# Motor_Controller.net
KiCad netlist of a schematic drawn in EAGLE
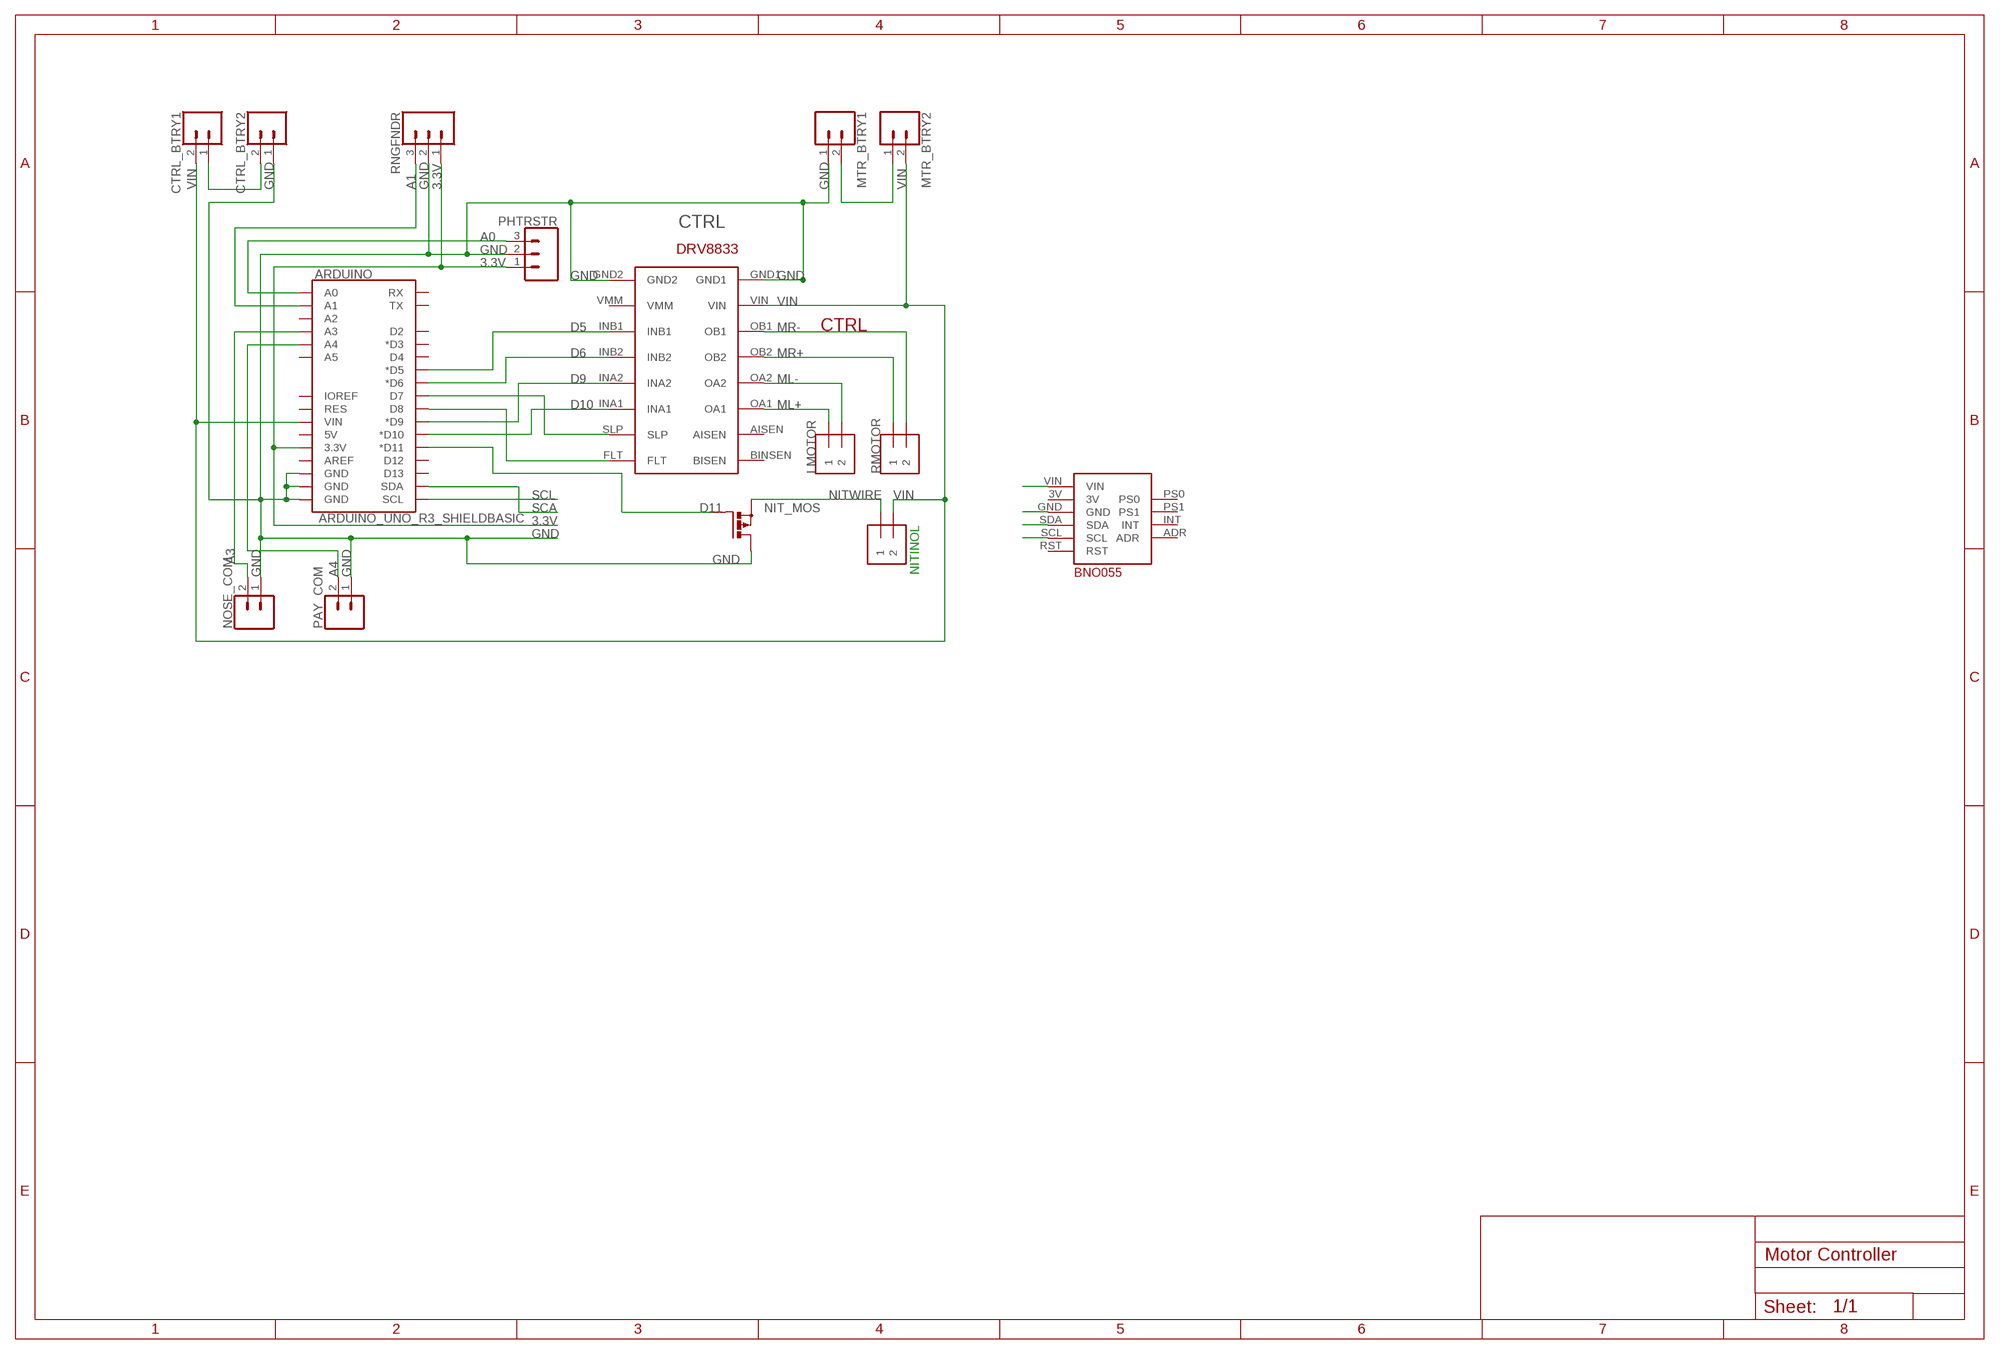
[diagram p0: schematic, sheet 1]

(export (version "E")
  (design (tool "Eeschema 10.0.6"))
  (components
    (comp (ref "ARDUINO")
      (value "ARDUINO_UNO_R3_SHIELDBASIC")
      (footprint "eagle-import:UNO_R3_SHIELD")
      (libsource (lib "eagle-import") (part "ARDUINO_UNO_R3_SHIELDBASIC"))
    )
    (comp (ref "CTRL")
      (value "POLOLU-DRV8833")
      (footprint "eagle-import:POLOLU-DRV8833")
      (libsource (lib "eagle-import") (part "POLOLU-DRV8833"))
    )
    (comp (ref "CTRL_BTRY1")
      (value "CONN_02-JST-2-PTH-NO_SILK")
      (footprint "eagle-import:JST-2-PTH-NS")
      (libsource (lib "eagle-import") (part "CONN_02-JST-2-PTH-NO_SILK"))
    )
    (comp (ref "CTRL_BTRY2")
      (value "CONN_02-JST-2-PTH-NO_SILK")
      (footprint "eagle-import:JST-2-PTH-NS")
      (libsource (lib "eagle-import") (part "CONN_02-JST-2-PTH-NO_SILK"))
    )
    (comp (ref "LMOTOR")
      (value "1X2-3.5MM")
      (footprint "eagle-import:1X2-3.5MM")
      (libsource (lib "eagle-import") (part "1X2-3.5MM"))
    )
    (comp (ref "MTR_BTRY1")
      (value "CONN_02-JST-2-PTH-NO_SILK")
      (footprint "eagle-import:JST-2-PTH-NS")
      (libsource (lib "eagle-import") (part "CONN_02-JST-2-PTH-NO_SILK"))
    )
    (comp (ref "MTR_BTRY2")
      (value "CONN_02-JST-2-PTH-NO_SILK")
      (footprint "eagle-import:JST-2-PTH-NS")
      (libsource (lib "eagle-import") (part "CONN_02-JST-2-PTH-NO_SILK"))
    )
    (comp (ref "NITINOL")
      (value "1X2-3.5MM")
      (footprint "eagle-import:1X2-3.5MM")
      (libsource (lib "eagle-import") (part "1X2-3.5MM"))
    )
    (comp (ref "NIT_MOS")
      (value "PMOSFET_PTO220BH")
      (footprint "eagle-import:TO220BH")
      (libsource (lib "eagle-import") (part "PMOSFET_PTO220BH"))
    )
    (comp (ref "NOSE_COM")
      (value "CONN_02JST-PTH-2")
      (footprint "eagle-import:JST-2-PTH")
      (libsource (lib "eagle-import") (part "CONN_02JST-PTH-2"))
    )
    (comp (ref "PAY_COM")
      (value "CONN_02JST-PTH-2")
      (footprint "eagle-import:JST-2-PTH")
      (libsource (lib "eagle-import") (part "CONN_02JST-PTH-2"))
    )
    (comp (ref "PHTRSTR")
      (value "CONN_03JST-PTH-NS")
      (footprint "eagle-import:JST-3-PTH-NS")
      (libsource (lib "eagle-import") (part "CONN_03JST-PTH-NS"))
    )
    (comp (ref "RMOTOR")
      (value "1X2-3.5MM")
      (footprint "eagle-import:1X2-3.5MM")
      (libsource (lib "eagle-import") (part "1X2-3.5MM"))
    )
    (comp (ref "RNGFNDR")
      (value "CONN_03JST-PTH-NS")
      (footprint "eagle-import:JST-3-PTH-NS")
      (libsource (lib "eagle-import") (part "CONN_03JST-PTH-NS"))
    )
    (comp (ref "U$1")
      (value "BNO055")
      (footprint "eagle-import:BNO055")
      (libsource (lib "eagle-import") (part "BNO055"))
    )
  )
  (nets
    (net (code "1") (name "/3.3V") (class "Default")
      (node (ref "ARDUINO") (pin "3.3V") (pinfunction "3.3V_3.3V") (pintype "bidirectional"))
      (node (ref "PHTRSTR") (pin "1") (pinfunction "1_1") (pintype "passive"))
      (node (ref "RNGFNDR") (pin "1") (pinfunction "1_1") (pintype "passive"))
      (node (ref "U$1") (pin "VIN") (pinfunction "VIN_VIN") (pintype "bidirectional"))
    )
    (net (code "2") (name "/A0") (class "Default")
      (node (ref "ARDUINO") (pin "A0") (pinfunction "A0_A0") (pintype "bidirectional"))
      (node (ref "PHTRSTR") (pin "3") (pinfunction "3_3") (pintype "passive"))
    )
    (net (code "3") (name "/A1") (class "Default")
      (node (ref "ARDUINO") (pin "A1") (pinfunction "A1_A1") (pintype "bidirectional"))
      (node (ref "RNGFNDR") (pin "3") (pinfunction "3_3") (pintype "passive"))
    )
    (net (code "4") (name "/A3") (class "Default")
      (node (ref "ARDUINO") (pin "A3") (pinfunction "A3_A3") (pintype "bidirectional"))
      (node (ref "NOSE_COM") (pin "2") (pinfunction "2_2") (pintype "passive"))
    )
    (net (code "5") (name "/A4") (class "Default")
      (node (ref "ARDUINO") (pin "A4") (pinfunction "A4_A4") (pintype "bidirectional"))
      (node (ref "PAY_COM") (pin "2") (pinfunction "2_2") (pintype "passive"))
    )
    (net (code "6") (name "/D5") (class "Default")
      (node (ref "ARDUINO") (pin "D5") (pinfunction "*D5_D5") (pintype "bidirectional"))
      (node (ref "CTRL") (pin "INB1") (pinfunction "INB1_INB1") (pintype "bidirectional"))
    )
    (net (code "7") (name "/D6") (class "Default")
      (node (ref "ARDUINO") (pin "D6") (pinfunction "*D6_D6") (pintype "bidirectional"))
      (node (ref "CTRL") (pin "INB2") (pinfunction "INB2_INB2") (pintype "bidirectional"))
    )
    (net (code "8") (name "/D9") (class "Default")
      (node (ref "ARDUINO") (pin "D9") (pinfunction "*D9_D9") (pintype "bidirectional"))
      (node (ref "CTRL") (pin "INA2") (pinfunction "INA2_INA2") (pintype "bidirectional"))
    )
    (net (code "9") (name "/D10") (class "Default")
      (node (ref "ARDUINO") (pin "D10") (pinfunction "*D10_D10") (pintype "bidirectional"))
      (node (ref "CTRL") (pin "INA1") (pinfunction "INA1_INA1") (pintype "bidirectional"))
    )
    (net (code "10") (name "/D11") (class "Default")
      (node (ref "ARDUINO") (pin "D11") (pinfunction "*D11_D11") (pintype "bidirectional"))
      (node (ref "NIT_MOS") (pin "G") (pinfunction "G_G") (pintype "passive"))
    )
    (net (code "11") (name "/GND") (class "Default")
      (node (ref "ARDUINO") (pin "GND@0") (pinfunction "GND_GND@0") (pintype "bidirectional"))
      (node (ref "ARDUINO") (pin "GND@1") (pinfunction "GND_GND@1") (pintype "bidirectional"))
      (node (ref "ARDUINO") (pin "GND@2") (pinfunction "GND_GND@2") (pintype "bidirectional"))
      (node (ref "CTRL") (pin "GND1") (pinfunction "GND1_GND1") (pintype "bidirectional"))
      (node (ref "CTRL") (pin "GND2") (pinfunction "GND2_GND2") (pintype "bidirectional"))
      (node (ref "CTRL_BTRY2") (pin "1") (pinfunction "1_1") (pintype "passive"))
      (node (ref "MTR_BTRY1") (pin "1") (pinfunction "1_1") (pintype "passive"))
      (node (ref "NIT_MOS") (pin "D") (pinfunction "D_D") (pintype "passive"))
      (node (ref "NOSE_COM") (pin "1") (pinfunction "1_1") (pintype "passive"))
      (node (ref "PAY_COM") (pin "1") (pinfunction "1_1") (pintype "passive"))
      (node (ref "PHTRSTR") (pin "2") (pinfunction "2_2") (pintype "passive"))
      (node (ref "RNGFNDR") (pin "2") (pinfunction "2_2") (pintype "passive"))
      (node (ref "U$1") (pin "GND") (pinfunction "GND_GND") (pintype "bidirectional"))
    )
    (net (code "12") (name "/ML+") (class "Default")
      (node (ref "CTRL") (pin "OA1") (pinfunction "OA1_OA1") (pintype "bidirectional"))
      (node (ref "LMOTOR") (pin "1") (pinfunction "1_1") (pintype "passive"))
    )
    (net (code "13") (name "/ML-") (class "Default")
      (node (ref "CTRL") (pin "OA2") (pinfunction "OA2_OA2") (pintype "bidirectional"))
      (node (ref "LMOTOR") (pin "2") (pinfunction "2_2") (pintype "passive"))
    )
    (net (code "14") (name "/MR+") (class "Default")
      (node (ref "CTRL") (pin "OB2") (pinfunction "OB2_OB2") (pintype "bidirectional"))
      (node (ref "RMOTOR") (pin "1") (pinfunction "1_1") (pintype "passive"))
    )
    (net (code "15") (name "/MR-") (class "Default")
      (node (ref "CTRL") (pin "OB1") (pinfunction "OB1_OB1") (pintype "bidirectional"))
      (node (ref "RMOTOR") (pin "2") (pinfunction "2_2") (pintype "passive"))
    )
    (net (code "16") (name "/NITWIRE") (class "Default")
      (node (ref "NITINOL") (pin "1") (pinfunction "1_1") (pintype "passive"))
      (node (ref "NIT_MOS") (pin "S") (pinfunction "S_S") (pintype "passive"))
    )
    (net (code "17") (name "/SCA") (class "Default")
      (node (ref "ARDUINO") (pin "SDA") (pinfunction "SDA_SDA") (pintype "bidirectional"))
      (node (ref "U$1") (pin "SDA") (pinfunction "SDA_SDA") (pintype "bidirectional"))
    )
    (net (code "18") (name "/SCL") (class "Default")
      (node (ref "ARDUINO") (pin "SCL") (pinfunction "SCL_SCL") (pintype "bidirectional"))
      (node (ref "U$1") (pin "SCL") (pinfunction "SCL_SCL") (pintype "bidirectional"))
    )
    (net (code "19") (name "/VIN") (class "Default")
      (node (ref "ARDUINO") (pin "VIN") (pinfunction "VIN_VIN") (pintype "bidirectional"))
      (node (ref "CTRL") (pin "VIN") (pinfunction "VIN_VIN") (pintype "bidirectional"))
      (node (ref "CTRL_BTRY1") (pin "2") (pinfunction "2_2") (pintype "passive"))
      (node (ref "MTR_BTRY2") (pin "2") (pinfunction "2_2") (pintype "passive"))
      (node (ref "NITINOL") (pin "2") (pinfunction "2_2") (pintype "passive"))
    )
    (net (code "20") (name "Net-(ARDUINO-PadD7)") (class "Default")
      (node (ref "ARDUINO") (pin "D7") (pinfunction "D7_D7") (pintype "bidirectional"))
      (node (ref "CTRL") (pin "SLP") (pinfunction "SLP_SLP") (pintype "bidirectional"))
    )
    (net (code "21") (name "Net-(ARDUINO-PadD8)") (class "Default")
      (node (ref "ARDUINO") (pin "D8") (pinfunction "D8_D8") (pintype "bidirectional"))
      (node (ref "CTRL") (pin "FLT") (pinfunction "FLT_FLT") (pintype "bidirectional"))
    )
    (net (code "22") (name "Net-(CTRL_BTRY1-Pad1)") (class "Default")
      (node (ref "CTRL_BTRY1") (pin "1") (pinfunction "1_1") (pintype "passive"))
      (node (ref "CTRL_BTRY2") (pin "2") (pinfunction "2_2") (pintype "passive"))
    )
    (net (code "23") (name "Net-(MTR_BTRY1-Pad2)") (class "Default")
      (node (ref "MTR_BTRY1") (pin "2") (pinfunction "2_2") (pintype "passive"))
      (node (ref "MTR_BTRY2") (pin "1") (pinfunction "1_1") (pintype "passive"))
    )
    (net (code "24") (name "unconnected-(ARDUINO-*D3-PadD3)") (class "Default")
      (node (ref "ARDUINO") (pin "D3") (pinfunction "*D3_D3") (pintype "bidirectional"))
    )
    (net (code "25") (name "unconnected-(ARDUINO-Pad5V)") (class "Default")
      (node (ref "ARDUINO") (pin "5V") (pinfunction "5V_5V") (pintype "bidirectional"))
    )
    (net (code "26") (name "unconnected-(ARDUINO-PadA2)") (class "Default")
      (node (ref "ARDUINO") (pin "A2") (pinfunction "A2_A2") (pintype "bidirectional"))
    )
    (net (code "27") (name "unconnected-(ARDUINO-PadA5)") (class "Default")
      (node (ref "ARDUINO") (pin "A5") (pinfunction "A5_A5") (pintype "bidirectional"))
    )
    (net (code "28") (name "unconnected-(ARDUINO-PadAREF)") (class "Default")
      (node (ref "ARDUINO") (pin "AREF") (pinfunction "AREF_AREF") (pintype "bidirectional"))
    )
    (net (code "29") (name "unconnected-(ARDUINO-PadD2)") (class "Default")
      (node (ref "ARDUINO") (pin "D2") (pinfunction "D2_D2") (pintype "bidirectional"))
    )
    (net (code "30") (name "unconnected-(ARDUINO-PadD4)") (class "Default")
      (node (ref "ARDUINO") (pin "D4") (pinfunction "D4_D4") (pintype "bidirectional"))
    )
    (net (code "31") (name "unconnected-(ARDUINO-PadD12)") (class "Default")
      (node (ref "ARDUINO") (pin "D12") (pinfunction "D12_D12") (pintype "bidirectional"))
    )
    (net (code "32") (name "unconnected-(ARDUINO-PadD13)") (class "Default")
      (node (ref "ARDUINO") (pin "D13") (pinfunction "D13_D13") (pintype "bidirectional"))
    )
    (net (code "33") (name "unconnected-(ARDUINO-PadIOREF)") (class "Default")
      (node (ref "ARDUINO") (pin "IOREF") (pinfunction "IOREF_IOREF") (pintype "bidirectional"))
    )
    (net (code "34") (name "unconnected-(ARDUINO-PadRES)") (class "Default")
      (node (ref "ARDUINO") (pin "RES") (pinfunction "RES_RES") (pintype "bidirectional"))
    )
    (net (code "35") (name "unconnected-(ARDUINO-PadRX)") (class "Default")
      (node (ref "ARDUINO") (pin "RX") (pinfunction "RX_RX") (pintype "bidirectional"))
    )
    (net (code "36") (name "unconnected-(ARDUINO-PadTX)") (class "Default")
      (node (ref "ARDUINO") (pin "TX") (pinfunction "TX_TX") (pintype "bidirectional"))
    )
    (net (code "37") (name "unconnected-(CTRL-BISEN-PadBINSEN)") (class "Default")
      (node (ref "CTRL") (pin "BINSEN") (pinfunction "BISEN_BINSEN") (pintype "bidirectional"))
    )
    (net (code "38") (name "unconnected-(CTRL-PadAISEN)") (class "Default")
      (node (ref "CTRL") (pin "AISEN") (pinfunction "AISEN_AISEN") (pintype "bidirectional"))
    )
    (net (code "39") (name "unconnected-(CTRL-PadVMM)") (class "Default")
      (node (ref "CTRL") (pin "VMM") (pinfunction "VMM_VMM") (pintype "output"))
    )
    (net (code "40") (name "unconnected-(U$1-Pad3V)") (class "Default")
      (node (ref "U$1") (pin "3V") (pinfunction "3V_3V") (pintype "bidirectional"))
    )
    (net (code "41") (name "unconnected-(U$1-PadADR)") (class "Default")
      (node (ref "U$1") (pin "ADR") (pinfunction "ADR_ADR") (pintype "bidirectional"))
    )
    (net (code "42") (name "unconnected-(U$1-PadINT)") (class "Default")
      (node (ref "U$1") (pin "INT") (pinfunction "INT_INT") (pintype "bidirectional"))
    )
    (net (code "43") (name "unconnected-(U$1-PadPS0)") (class "Default")
      (node (ref "U$1") (pin "PS0") (pinfunction "PS0_PS0") (pintype "bidirectional"))
    )
    (net (code "44") (name "unconnected-(U$1-PadPS1)") (class "Default")
      (node (ref "U$1") (pin "PS1") (pinfunction "PS1_PS1") (pintype "bidirectional"))
    )
    (net (code "45") (name "unconnected-(U$1-PadRST)") (class "Default")
      (node (ref "U$1") (pin "RST") (pinfunction "RST_RST") (pintype "bidirectional"))
    )
  )
)
